# OSSC_HDMI_Audio_v1_5_A4a.net
KiCad netlist of a schematic drawn in EAGLE
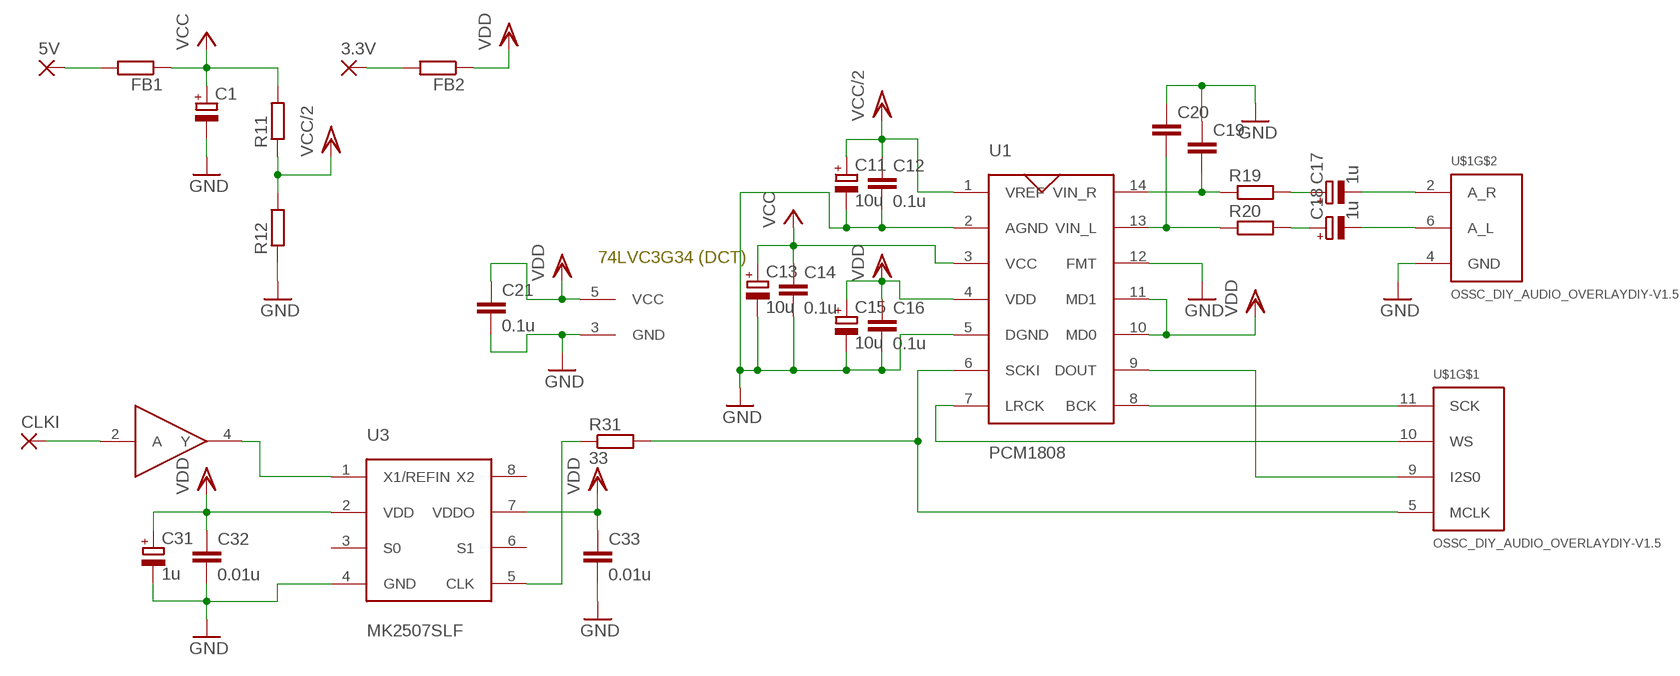
[diagram p0: schematic, sheet 1]

(export (version "E")
  (design (tool "Eeschema 10.0.6"))
  (components
    (comp (ref "3.3V")
      (value "SMD2")
      (footprint "eagle-import:SMD1,27-2,54")
      (libsource (lib "eagle-import") (part "SMD2"))
    )
    (comp (ref "5V")
      (value "SMD2")
      (footprint "eagle-import:SMD1,27-2,54")
      (libsource (lib "eagle-import") (part "SMD2"))
    )
    (comp (ref "C1")
      (value "CPOL-EUSMCC")
      (footprint "eagle-import:SMC_C")
      (libsource (lib "eagle-import") (part "CPOL-EUSMCC"))
    )
    (comp (ref "C11")
      (value "10u")
      (footprint "eagle-import:SMC_A")
      (libsource (lib "eagle-import") (part "CPOL-EUSMCA"))
    )
    (comp (ref "C12")
      (value "0.1u")
      (footprint "eagle-import:C0603")
      (libsource (lib "eagle-import") (part "C-EUC0603"))
    )
    (comp (ref "C13")
      (value "10u")
      (footprint "eagle-import:SMC_A")
      (libsource (lib "eagle-import") (part "CPOL-EUSMCA"))
    )
    (comp (ref "C14")
      (value "0.1u")
      (footprint "eagle-import:C0603")
      (libsource (lib "eagle-import") (part "C-EUC0603"))
    )
    (comp (ref "C15")
      (value "10u")
      (footprint "eagle-import:SMC_A")
      (libsource (lib "eagle-import") (part "CPOL-EUSMCA"))
    )
    (comp (ref "C16")
      (value "0.1u")
      (footprint "eagle-import:C0603")
      (libsource (lib "eagle-import") (part "C-EUC0603"))
    )
    (comp (ref "C17")
      (value "1u")
      (footprint "eagle-import:SMC_A")
      (libsource (lib "eagle-import") (part "CPOL-EUSMCA"))
    )
    (comp (ref "C18")
      (value "1u")
      (footprint "eagle-import:SMC_A")
      (libsource (lib "eagle-import") (part "CPOL-EUSMCA"))
    )
    (comp (ref "C19")
      (value "C-EUC0603")
      (footprint "eagle-import:C0603")
      (libsource (lib "eagle-import") (part "C-EUC0603"))
    )
    (comp (ref "C20")
      (value "C-EUC0603")
      (footprint "eagle-import:C0603")
      (libsource (lib "eagle-import") (part "C-EUC0603"))
    )
    (comp (ref "C21")
      (value "0.1u")
      (footprint "eagle-import:C0603")
      (libsource (lib "eagle-import") (part "C-EUC0603"))
    )
    (comp (ref "C31")
      (value "1u")
      (footprint "eagle-import:SMC_A")
      (libsource (lib "eagle-import") (part "CPOL-EUSMCA"))
    )
    (comp (ref "C32")
      (value "0.01u")
      (footprint "eagle-import:C0603")
      (libsource (lib "eagle-import") (part "C-EUC0603"))
    )
    (comp (ref "C33")
      (value "0.01u")
      (footprint "eagle-import:C0603")
      (libsource (lib "eagle-import") (part "C-EUC0603"))
    )
    (comp (ref "CLKI")
      (value "SMD2")
      (footprint "eagle-import:SMD1,27-2,54")
      (libsource (lib "eagle-import") (part "SMD2"))
    )
    (comp (ref "FB1")
      (value "R-EU_R0603")
      (footprint "eagle-import:R0603")
      (libsource (lib "eagle-import") (part "R-EU_R0603"))
    )
    (comp (ref "FB2")
      (value "R-EU_R0603")
      (footprint "eagle-import:R0603")
      (libsource (lib "eagle-import") (part "R-EU_R0603"))
    )
    (comp (ref "R11")
      (value "R-EU_R0603")
      (footprint "eagle-import:R0603")
      (libsource (lib "eagle-import") (part "R-EU_R0603"))
    )
    (comp (ref "R12")
      (value "R-EU_R0603")
      (footprint "eagle-import:R0603")
      (libsource (lib "eagle-import") (part "R-EU_R0603"))
    )
    (comp (ref "R19")
      (value "R-EU_R0603")
      (footprint "eagle-import:R0603")
      (libsource (lib "eagle-import") (part "R-EU_R0603"))
    )
    (comp (ref "R20")
      (value "R-EU_R0603")
      (footprint "eagle-import:R0603")
      (libsource (lib "eagle-import") (part "R-EU_R0603"))
    )
    (comp (ref "R31")
      (value "33")
      (footprint "eagle-import:R0603")
      (libsource (lib "eagle-import") (part "R-EU_R0603"))
    )
    (comp (ref "U$1")
      (value "OSSC_DIY_AUDIO_OVERLAYDIY-V1.5")
      (footprint "eagle-import:OSSC_OVERLAY_V1.5")
      (libsource (lib "eagle-import") (part "OSSC_DIY_AUDIO_OVERLAYDIY-V1.5"))
    )
    (comp (ref "U1")
      (value "PCM1808")
      (footprint "eagle-import:PCM1808")
      (libsource (lib "eagle-import") (part "PCM1808"))
    )
    (comp (ref "U2")
      (value "74LVC1G34")
      (footprint "eagle-import:74LVC1G34DCK")
      (libsource (lib "eagle-import") (part "74LVC1G34"))
    )
    (comp (ref "U3")
      (value "MK2507SLF")
      (footprint "eagle-import:SOIC8")
      (libsource (lib "eagle-import") (part "MK2507SLF"))
    )
  )
  (nets
    (net (code "1") (name "GND") (class "Default")
      (node (ref "C1") (pin "-") (pinfunction "-_-") (pintype "passive"))
      (node (ref "C11") (pin "-") (pinfunction "-_-") (pintype "passive"))
      (node (ref "C12") (pin "2") (pinfunction "2_2") (pintype "passive"))
      (node (ref "C13") (pin "-") (pinfunction "-_-") (pintype "passive"))
      (node (ref "C14") (pin "2") (pinfunction "2_2") (pintype "passive"))
      (node (ref "C15") (pin "-") (pinfunction "-_-") (pintype "passive"))
      (node (ref "C16") (pin "2") (pinfunction "2_2") (pintype "passive"))
      (node (ref "C19") (pin "1") (pinfunction "1_1") (pintype "passive"))
      (node (ref "C20") (pin "1") (pinfunction "1_1") (pintype "passive"))
      (node (ref "C21") (pin "2") (pinfunction "2_2") (pintype "passive"))
      (node (ref "C31") (pin "-") (pinfunction "-_-") (pintype "passive"))
      (node (ref "C32") (pin "2") (pinfunction "2_2") (pintype "passive"))
      (node (ref "C33") (pin "2") (pinfunction "2_2") (pintype "passive"))
      (node (ref "R12") (pin "1") (pinfunction "1_1") (pintype "passive"))
      (node (ref "U$1") (pin "4") (pinfunction "GND_4") (pintype "bidirectional"))
      (node (ref "U1") (pin "12") (pinfunction "FMT_12") (pintype "bidirectional"))
      (node (ref "U1") (pin "2") (pinfunction "AGND_2") (pintype "bidirectional"))
      (node (ref "U1") (pin "5") (pinfunction "DGND_5") (pintype "bidirectional"))
      (node (ref "U2") (pin "3") (pinfunction "GND_3") (pintype "bidirectional"))
      (node (ref "U3") (pin "4") (pinfunction "GND_4") (pintype "bidirectional"))
    )
    (net (code "2") (name "Net-(3.3V-P)") (class "Default")
      (node (ref "3.3V") (pin "1") (pinfunction "P_1") (pintype "passive"))
      (node (ref "FB2") (pin "2") (pinfunction "2_2") (pintype "passive"))
    )
    (net (code "3") (name "Net-(5V-P)") (class "Default")
      (node (ref "5V") (pin "1") (pinfunction "P_1") (pintype "passive"))
      (node (ref "FB1") (pin "2") (pinfunction "2_2") (pintype "passive"))
    )
    (net (code "4") (name "Net-(C17-Pad+)") (class "Default")
      (node (ref "C17") (pin "+") (pinfunction "+_+") (pintype "passive"))
      (node (ref "R19") (pin "2") (pinfunction "2_2") (pintype "passive"))
    )
    (net (code "5") (name "Net-(C18-Pad+)") (class "Default")
      (node (ref "C18") (pin "+") (pinfunction "+_+") (pintype "passive"))
      (node (ref "R20") (pin "2") (pinfunction "2_2") (pintype "passive"))
    )
    (net (code "6") (name "Net-(CLKI-P)") (class "Default")
      (node (ref "CLKI") (pin "1") (pinfunction "P_1") (pintype "passive"))
      (node (ref "U2") (pin "2") (pinfunction "A_2") (pintype "bidirectional"))
    )
    (net (code "7") (name "Net-(U$1A-I2S0)") (class "Default")
      (node (ref "U$1") (pin "9") (pinfunction "I2S0_9") (pintype "bidirectional"))
      (node (ref "U1") (pin "9") (pinfunction "DOUT_9") (pintype "bidirectional"))
    )
    (net (code "8") (name "Net-(U$1A-MCLK)") (class "Default")
      (node (ref "R31") (pin "2") (pinfunction "2_2") (pintype "passive"))
      (node (ref "U$1") (pin "5") (pinfunction "MCLK_5") (pintype "bidirectional"))
      (node (ref "U1") (pin "6") (pinfunction "SCKI_6") (pintype "bidirectional"))
    )
    (net (code "9") (name "Net-(U$1A-SCK)") (class "Default")
      (node (ref "U$1") (pin "11") (pinfunction "SCK_11") (pintype "bidirectional"))
      (node (ref "U1") (pin "8") (pinfunction "BCK_8") (pintype "bidirectional"))
    )
    (net (code "10") (name "Net-(U$1A-WS)") (class "Default")
      (node (ref "U$1") (pin "10") (pinfunction "WS_10") (pintype "bidirectional"))
      (node (ref "U1") (pin "7") (pinfunction "LRCK_7") (pintype "bidirectional"))
    )
    (net (code "11") (name "Net-(U$1B-A_L)") (class "Default")
      (node (ref "C18") (pin "-") (pinfunction "-_-") (pintype "passive"))
      (node (ref "U$1") (pin "6") (pinfunction "A_L_6") (pintype "bidirectional"))
    )
    (net (code "12") (name "Net-(U$1B-A_R)") (class "Default")
      (node (ref "C17") (pin "-") (pinfunction "-_-") (pintype "passive"))
      (node (ref "U$1") (pin "2") (pinfunction "A_R_2") (pintype "bidirectional"))
    )
    (net (code "13") (name "Net-(U1-VIN_L)") (class "Default")
      (node (ref "C20") (pin "2") (pinfunction "2_2") (pintype "passive"))
      (node (ref "R20") (pin "1") (pinfunction "1_1") (pintype "passive"))
      (node (ref "U1") (pin "13") (pinfunction "VIN_L_13") (pintype "bidirectional"))
    )
    (net (code "14") (name "Net-(U1-VIN_R)") (class "Default")
      (node (ref "C19") (pin "2") (pinfunction "2_2") (pintype "passive"))
      (node (ref "R19") (pin "1") (pinfunction "1_1") (pintype "passive"))
      (node (ref "U1") (pin "14") (pinfunction "VIN_R_14") (pintype "bidirectional"))
    )
    (net (code "15") (name "Net-(U2A-Y)") (class "Default")
      (node (ref "U2") (pin "4") (pinfunction "Y_4") (pintype "bidirectional"))
      (node (ref "U3") (pin "1") (pinfunction "X1/REFIN_1") (pintype "bidirectional"))
    )
    (net (code "16") (name "Net-(U3-CLK)") (class "Default")
      (node (ref "R31") (pin "1") (pinfunction "1_1") (pintype "passive"))
      (node (ref "U3") (pin "5") (pinfunction "CLK_5") (pintype "bidirectional"))
    )
    (net (code "17") (name "VCC") (class "Default")
      (node (ref "C1") (pin "+") (pinfunction "+_+") (pintype "passive"))
      (node (ref "C13") (pin "+") (pinfunction "+_+") (pintype "passive"))
      (node (ref "C14") (pin "1") (pinfunction "1_1") (pintype "passive"))
      (node (ref "FB1") (pin "1") (pinfunction "1_1") (pintype "passive"))
      (node (ref "R11") (pin "2") (pinfunction "2_2") (pintype "passive"))
      (node (ref "U1") (pin "3") (pinfunction "VCC_3") (pintype "bidirectional"))
    )
    (net (code "18") (name "VCC{slash}2") (class "Default")
      (node (ref "C11") (pin "+") (pinfunction "+_+") (pintype "passive"))
      (node (ref "C12") (pin "1") (pinfunction "1_1") (pintype "passive"))
      (node (ref "R11") (pin "1") (pinfunction "1_1") (pintype "passive"))
      (node (ref "R12") (pin "2") (pinfunction "2_2") (pintype "passive"))
      (node (ref "U1") (pin "1") (pinfunction "VREF_1") (pintype "bidirectional"))
    )
    (net (code "19") (name "VDD") (class "Default")
      (node (ref "C15") (pin "+") (pinfunction "+_+") (pintype "passive"))
      (node (ref "C16") (pin "1") (pinfunction "1_1") (pintype "passive"))
      (node (ref "C21") (pin "1") (pinfunction "1_1") (pintype "passive"))
      (node (ref "C31") (pin "+") (pinfunction "+_+") (pintype "passive"))
      (node (ref "C32") (pin "1") (pinfunction "1_1") (pintype "passive"))
      (node (ref "C33") (pin "1") (pinfunction "1_1") (pintype "passive"))
      (node (ref "FB2") (pin "1") (pinfunction "1_1") (pintype "passive"))
      (node (ref "U1") (pin "10") (pinfunction "MD0_10") (pintype "bidirectional"))
      (node (ref "U1") (pin "11") (pinfunction "MD1_11") (pintype "bidirectional"))
      (node (ref "U1") (pin "4") (pinfunction "VDD_4") (pintype "bidirectional"))
      (node (ref "U2") (pin "5") (pinfunction "VCC_5") (pintype "bidirectional"))
      (node (ref "U3") (pin "2") (pinfunction "VDD_2") (pintype "bidirectional"))
      (node (ref "U3") (pin "7") (pinfunction "VDDO_7") (pintype "bidirectional"))
    )
    (net (code "20") (name "unconnected-(U3-S0-Pad3)") (class "Default")
      (node (ref "U3") (pin "3") (pinfunction "S0_3") (pintype "bidirectional"))
    )
    (net (code "21") (name "unconnected-(U3-S1-Pad6)") (class "Default")
      (node (ref "U3") (pin "6") (pinfunction "S1_6") (pintype "bidirectional"))
    )
    (net (code "22") (name "unconnected-(U3-X2-Pad8)") (class "Default")
      (node (ref "U3") (pin "8") (pinfunction "X2_8") (pintype "bidirectional"))
    )
  )
)
